# SerialCommunication.net
KiCad netlist of a schematic drawn in Altium Designer
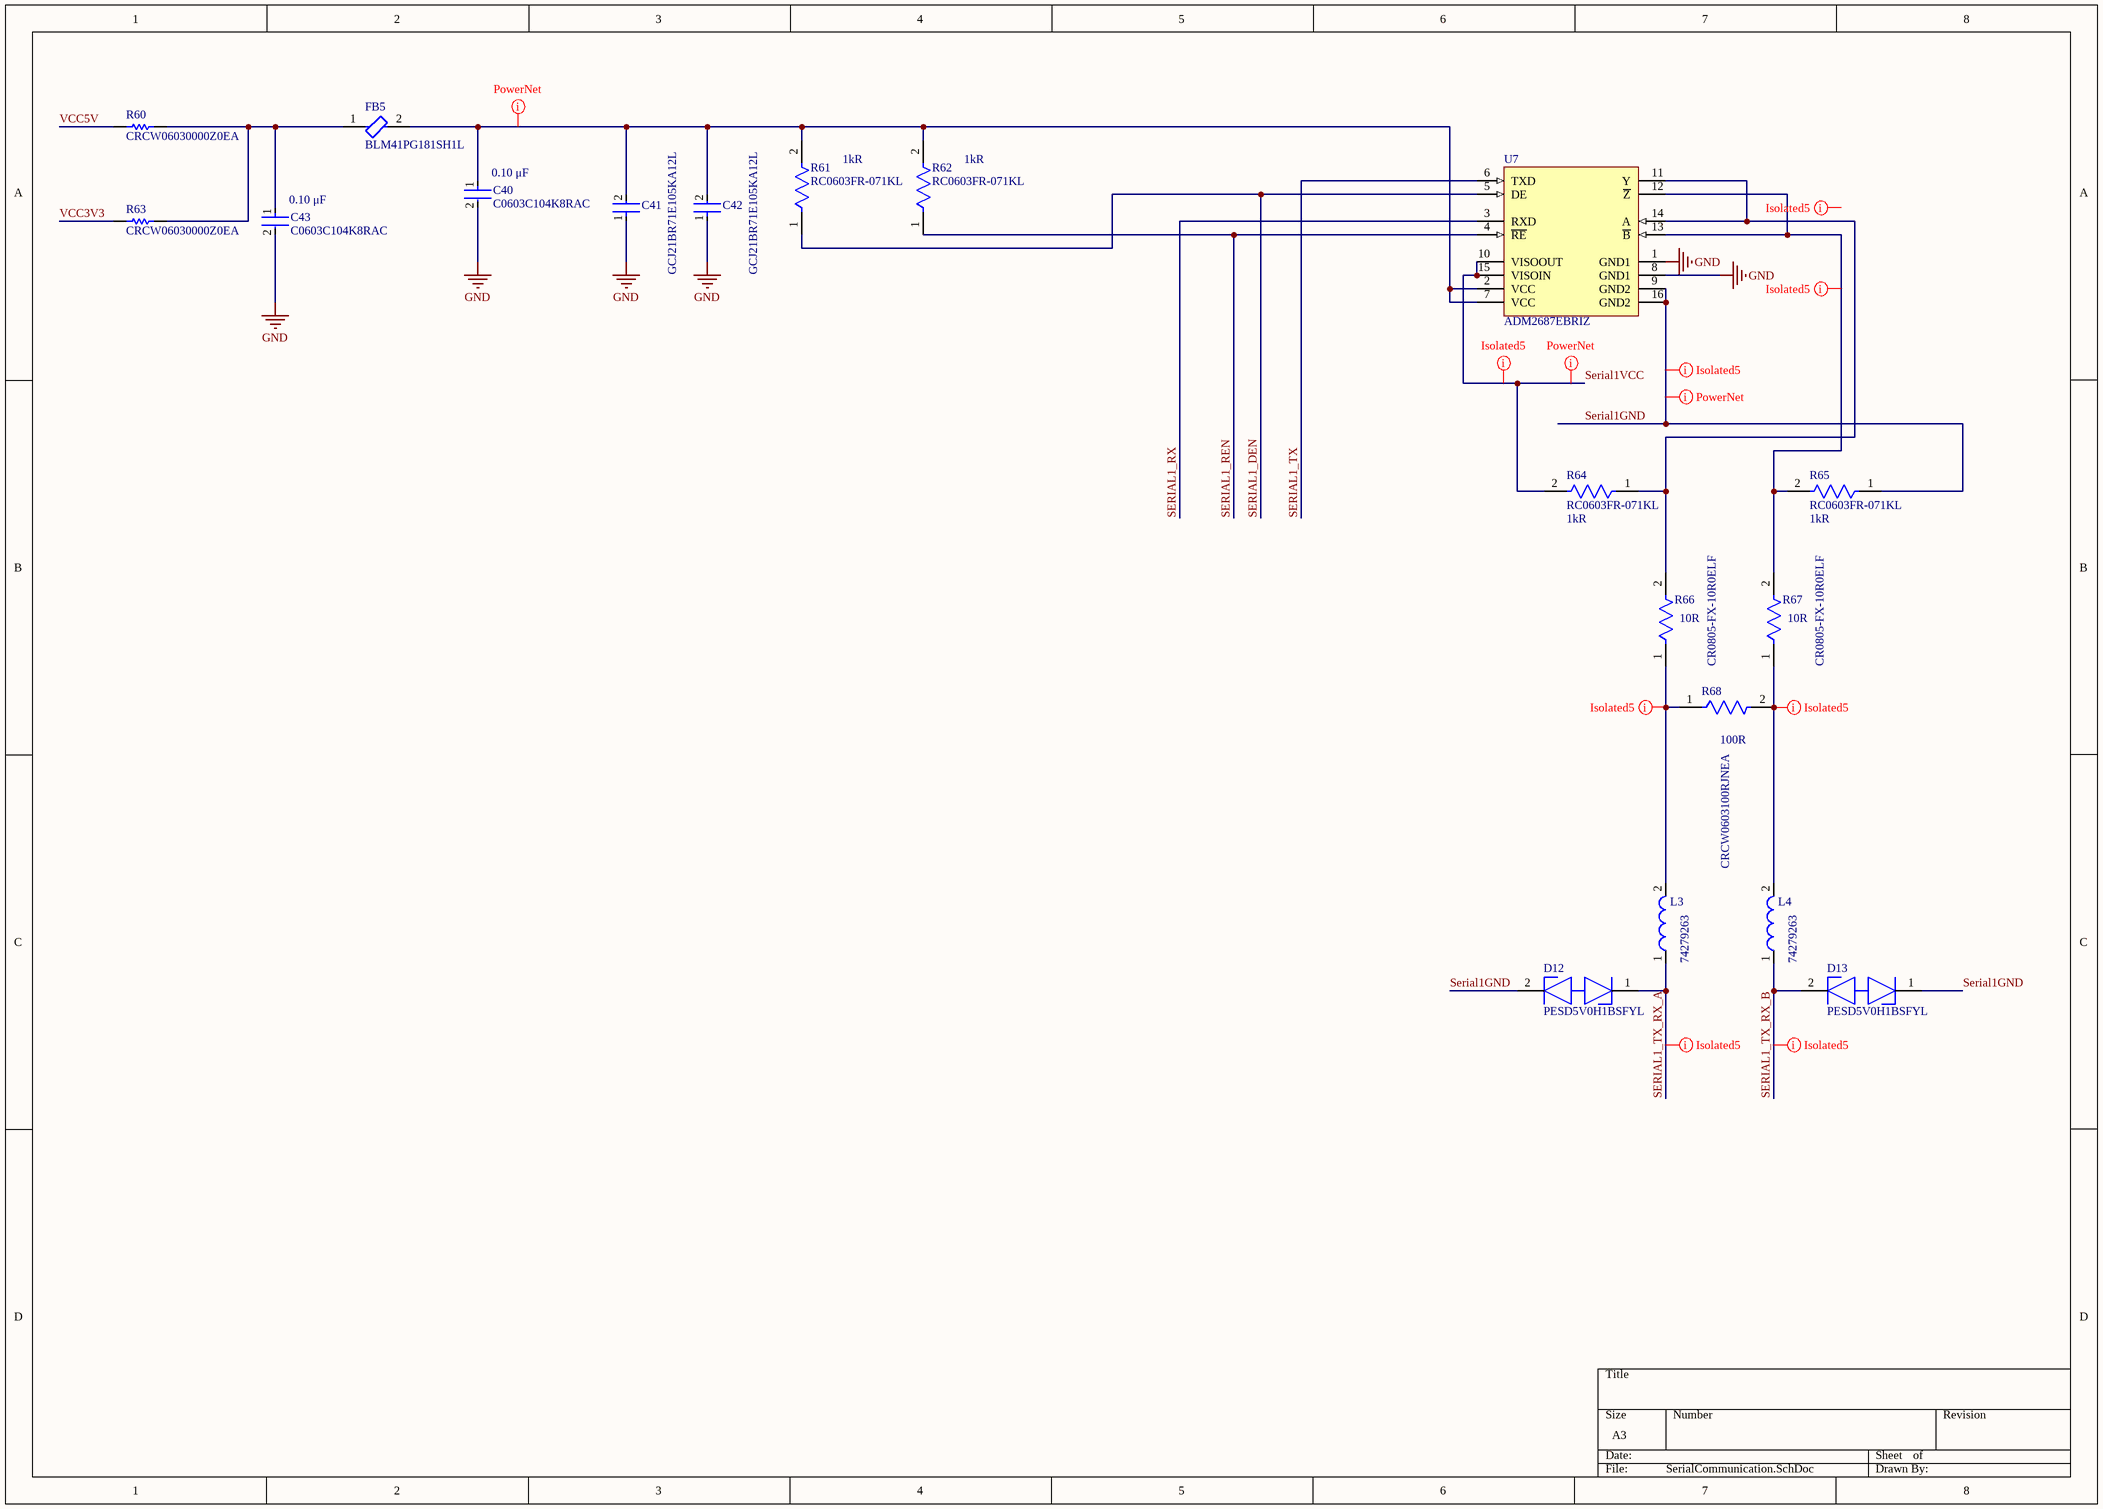
[diagram p0: SerialCommunication.SchDoc]

(export (version "E")
  (design (tool "Eeschema 10.0.6"))
  (components
    (comp (ref "C40")
      (value "C0603C104K8RAC")
      (footprint "FP-C0603C-CF-MFG")
      (description "C0603 0.10 μF X7R 30ppm/°C 10.00% 10 V")
      (fields
        (field (name "MANUFACTURER") "KEMET")
        (field (name "CAPACITANCE") "0.10 μF")
        (field (name "OCTOPART") "https://octopart.com/c0603c104k8rac-kemet-1325403")
      )
      (libsource (lib "Altium Content Vault") (part "b4654b650e69147ec39a6b967a45e02"))
    )
    (comp (ref "C41")
      (value "GCJ21BR71E105KA12L")
      (footprint "FP-GCJ21B-0_3-MFG")
      (description "Multilayer Ceramic Capacitors MLCC - SMD/SMT 0805 1uF 10%, 25VDC,  X7R 15%")
      (fields (field (name "TOLERANCE") "10%"))
      (libsource (lib "Altium Content Vault") (part "02cd4be3c70576c341d710602a673aa"))
    )
    (comp (ref "C42")
      (value "GCJ21BR71E105KA12L")
      (footprint "FP-GCJ21B-0_3-MFG")
      (description "Multilayer Ceramic Capacitors MLCC - SMD/SMT 0805 1uF 10%, 25VDC,  X7R 15%")
      (fields (field (name "TOLERANCE") "10%"))
      (libsource (lib "Altium Content Vault") (part "02cd4be3c70576c341d710602a673aa"))
    )
    (comp (ref "C43")
      (value "C0603C104K8RAC")
      (footprint "FP-C0603C-CF-MFG")
      (description "C0603 0.10 μF X7R 30ppm/°C 10.00% 10 V")
      (fields
        (field (name "MANUFACTURER") "KEMET")
        (field (name "CAPACITANCE") "0.10 μF")
        (field (name "OCTOPART") "https://octopart.com/c0603c104k8rac-kemet-1325403")
      )
      (libsource (lib "Altium Content Vault") (part "b4654b650e69147ec39a6b967a45e02"))
    )
    (comp (ref "D12")
      (value "PESD5V0H1BSFYL")
      (footprint "FP-SOD962-2-MFG")
      (description "TVS DIODE 5V 5V DSN0603-2")
      (fields
        (field (name "OCTOPART") "https://octopart.com/pesd5v0h1bsfyl-nexperia-78741149")
        (field (name "MANUFACTURER") "Nexperia")
      )
      (libsource (lib "Altium Content Vault") (part "35d3c4067516f6c39e60198d779250f"))
    )
    (comp (ref "D13")
      (value "PESD5V0H1BSFYL")
      (footprint "FP-SOD962-2-MFG")
      (description "TVS DIODE 5V 5V DSN0603-2")
      (fields
        (field (name "OCTOPART") "https://octopart.com/pesd5v0h1bsfyl-nexperia-78741149")
        (field (name "MANUFACTURER") "Nexperia")
      )
      (libsource (lib "Altium Content Vault") (part "35d3c4067516f6c39e60198d779250f"))
    )
    (comp (ref "FB5")
      (value "BLM41PG181SH1L")
      (footprint "FP-BLM41-0_2-a1_2-MFG")
      (description "Ferrite Bead, 1806, 180Ω @ 100MHz, 25%, 0.02Ω, 3.5A")
      (fields (field (name "TOLERANCE") "25%"))
      (libsource (lib "Altium Content Vault") (part "5f30dd21d616792df468990f7003faa"))
    )
    (comp (ref "L3")
      (value "74279263")
      (footprint "SMD-0603")
      (description "SMD EMI Suppression Ferrite Bead WE-CBF, Z = 220 Ohm")
      (libsource (lib "Altium Content Vault") (part "PAS-IND-INDUCTOR-2"))
    )
    (comp (ref "L4")
      (value "74279263")
      (footprint "SMD-0603")
      (description "SMD EMI Suppression Ferrite Bead WE-CBF, Z = 220 Ohm")
      (libsource (lib "Altium Content Vault") (part "PAS-IND-INDUCTOR-2"))
    )
    (comp (ref "R60")
      (value "CRCW06030000Z0EA")
      (footprint "RESC1609X50X30NL8T20")
      (description "Chip Resistor, 0 Ohm, Jumper, 100 mW, -55 to 155 degC, 0603 (1608 Metric), RoHS, Tape and Reel")
      (fields (field (name "MANUFACTURER") "Vishay Semiconductor"))
      (libsource (lib "Altium Content Vault") (part "RES-2"))
    )
    (comp (ref "R61")
      (value "RC0603FR-071KL")
      (footprint "FP-RC0603-0_55-IPC_C")
      (description "RES 1K OHM 1% 1/10W 0603")
      (fields (field (name "RESISTANCE") "1kR") (field (name "TOLERANCE") "1%"))
      (libsource (lib "Altium Content Vault") (part "1029c3af85768c4190bb7ad29bc67b5"))
    )
    (comp (ref "R62")
      (value "RC0603FR-071KL")
      (footprint "FP-RC0603-0_55-IPC_C")
      (description "RES 1K OHM 1% 1/10W 0603")
      (fields (field (name "RESISTANCE") "1kR") (field (name "TOLERANCE") "1%"))
      (libsource (lib "Altium Content Vault") (part "1029c3af85768c4190bb7ad29bc67b5"))
    )
    (comp (ref "R63")
      (value "CRCW06030000Z0EA")
      (footprint "RESC1609X50X30NL8T20")
      (description "Chip Resistor, 0 Ohm, Jumper, 100 mW, -55 to 155 degC, 0603 (1608 Metric), RoHS, Tape and Reel")
      (fields (field (name "MANUFACTURER") "Vishay Semiconductor"))
      (libsource (lib "Altium Content Vault") (part "RES-2"))
    )
    (comp (ref "R64")
      (value "RC0603FR-071KL")
      (footprint "FP-RC0603-0_55-IPC_C")
      (description "RES 1K OHM 1% 1/10W 0603")
      (fields (field (name "RESISTANCE") "1kR") (field (name "TOLERANCE") "1%"))
      (libsource (lib "Altium Content Vault") (part "1029c3af85768c4190bb7ad29bc67b5"))
    )
    (comp (ref "R65")
      (value "RC0603FR-071KL")
      (footprint "FP-RC0603-0_55-IPC_C")
      (description "RES 1K OHM 1% 1/10W 0603")
      (fields (field (name "RESISTANCE") "1kR") (field (name "TOLERANCE") "1%"))
      (libsource (lib "Altium Content Vault") (part "1029c3af85768c4190bb7ad29bc67b5"))
    )
    (comp (ref "R66")
      (value "CR0805-FX-10R0ELF")
      (footprint "FP-CR0805-IPC_B")
      (description "Thick Film Chip Resistors 0805 10Ω 0.125W 1% 100ppm/°C")
      (fields (field (name "TOLERANCE") "1%") (field (name "RESISTANCE") "10R"))
      (libsource (lib "Altium Content Vault") (part "1029c3af85768c4190bb7ad29bc67b5"))
    )
    (comp (ref "R67")
      (value "CR0805-FX-10R0ELF")
      (footprint "FP-CR0805-IPC_B")
      (description "Thick Film Chip Resistors 0805 10Ω 0.125W 1% 100ppm/°C")
      (fields (field (name "TOLERANCE") "1%") (field (name "RESISTANCE") "10R"))
      (libsource (lib "Altium Content Vault") (part "1029c3af85768c4190bb7ad29bc67b5"))
    )
    (comp (ref "R68")
      (value "CRCW0603100RJNEA")
      (footprint "FP-CRCW0603-e3-IPC_B")
      (description "RES Thick Film, 100Ω, 5%, 0.1W, 200ppm/°C, 0603")
      (fields (field (name "RESISTANCE") "100R") (field (name "TOLERANCE") "5%"))
      (libsource (lib "Altium Content Vault") (part "1029c3af85768c4190bb7ad29bc67b5"))
    )
    (comp (ref "U7")
      (value "ADM2687EBRIZ")
      (footprint "ADI-RI-16-2_L")
      (fields (field (name "MANUFACTURER") "Analog Devices"))
      (libsource (lib "Altium Content Vault") (part "ADI-ADM268X-RI-16-2"))
    )
  )
  (nets
    (net (code "1") (name "/SERIAL1_DEN") (class "Default")
      (node (ref "R61") (pin "1") (pinfunction "1_1") (pintype "passive"))
      (node (ref "U7") (pin "5") (pinfunction "DE_5") (pintype "input"))
    )
    (net (code "2") (name "/SERIAL1_REN") (class "Default")
      (node (ref "R62") (pin "1") (pinfunction "1_1") (pintype "passive"))
      (node (ref "U7") (pin "4") (pinfunction "~{RE}_4") (pintype "input"))
    )
    (net (code "3") (name "/SERIAL1_RX") (class "Default")
      (node (ref "U7") (pin "3") (pinfunction "RXD_3") (pintype "tri_state"))
    )
    (net (code "4") (name "/SERIAL1_TX") (class "Default")
      (node (ref "U7") (pin "6") (pinfunction "TXD_6") (pintype "input"))
    )
    (net (code "5") (name "/SERIAL1_TX_RX_A") (class "Default")
      (node (ref "D12") (pin "1") (pinfunction "K1_1") (pintype "passive"))
      (node (ref "L3") (pin "1") (pinfunction "1_1") (pintype "passive"))
    )
    (net (code "6") (name "/SERIAL1_TX_RX_B") (class "Default")
      (node (ref "D13") (pin "2") (pinfunction "K2_2") (pintype "passive"))
      (node (ref "L4") (pin "1") (pinfunction "1_1") (pintype "passive"))
    )
    (net (code "7") (name "/Serial1GND") (class "Default")
      (node (ref "D12") (pin "2") (pinfunction "K2_2") (pintype "passive"))
      (node (ref "D13") (pin "1") (pinfunction "K1_1") (pintype "passive"))
      (node (ref "R65") (pin "1") (pinfunction "1_1") (pintype "passive"))
      (node (ref "U7") (pin "16") (pinfunction "GND2_16") (pintype "power_in"))
      (node (ref "U7") (pin "9") (pinfunction "GND2_9") (pintype "power_in"))
    )
    (net (code "8") (name "/Serial1VCC") (class "Default")
      (node (ref "R64") (pin "2") (pinfunction "2_2") (pintype "passive"))
      (node (ref "U7") (pin "10") (pinfunction "VISOOUT_10") (pintype "power_in"))
      (node (ref "U7") (pin "15") (pinfunction "VISOIN_15") (pintype "power_in"))
    )
    (net (code "9") (name "/VCC3V3") (class "Default")
      (node (ref "R63") (pin "1") (pinfunction "1_1") (pintype "passive"))
    )
    (net (code "10") (name "/VCC5V") (class "Default")
      (node (ref "R60") (pin "1") (pinfunction "1_1") (pintype "passive"))
    )
    (net (code "11") (name "GND") (class "Default")
      (node (ref "C40") (pin "2") (pinfunction "2_2") (pintype "passive"))
      (node (ref "C41") (pin "1") (pinfunction "1_1") (pintype "passive"))
      (node (ref "C42") (pin "1") (pinfunction "1_1") (pintype "passive"))
      (node (ref "C43") (pin "2") (pinfunction "2_2") (pintype "passive"))
      (node (ref "U7") (pin "1") (pinfunction "GND1_1") (pintype "power_in"))
      (node (ref "U7") (pin "8") (pinfunction "GND1_8") (pintype "power_in"))
    )
    (net (code "12") (name "Net-(C40-Pad1)") (class "Default")
      (node (ref "C40") (pin "1") (pinfunction "1_1") (pintype "passive"))
      (node (ref "C41") (pin "2") (pinfunction "2_2") (pintype "passive"))
      (node (ref "C42") (pin "2") (pinfunction "2_2") (pintype "passive"))
      (node (ref "FB5") (pin "2") (pinfunction "2_2") (pintype "passive"))
      (node (ref "R61") (pin "2") (pinfunction "2_2") (pintype "passive"))
      (node (ref "R62") (pin "2") (pinfunction "2_2") (pintype "passive"))
      (node (ref "U7") (pin "2") (pinfunction "VCC_2") (pintype "power_in"))
      (node (ref "U7") (pin "7") (pinfunction "VCC_7") (pintype "power_in"))
    )
    (net (code "13") (name "Net-(C43-Pad1)") (class "Default")
      (node (ref "C43") (pin "1") (pinfunction "1_1") (pintype "passive"))
      (node (ref "FB5") (pin "1") (pinfunction "1_1") (pintype "passive"))
      (node (ref "R60") (pin "2") (pinfunction "2_2") (pintype "passive"))
      (node (ref "R63") (pin "2") (pinfunction "2_2") (pintype "passive"))
    )
    (net (code "14") (name "Net-(L3-Pad2)") (class "Default")
      (node (ref "L3") (pin "2") (pinfunction "2_2") (pintype "passive"))
      (node (ref "R66") (pin "1") (pinfunction "1_1") (pintype "passive"))
      (node (ref "R68") (pin "1") (pinfunction "1_1") (pintype "passive"))
    )
    (net (code "15") (name "Net-(L4-Pad2)") (class "Default")
      (node (ref "L4") (pin "2") (pinfunction "2_2") (pintype "passive"))
      (node (ref "R67") (pin "1") (pinfunction "1_1") (pintype "passive"))
      (node (ref "R68") (pin "2") (pinfunction "2_2") (pintype "passive"))
    )
    (net (code "16") (name "Net-(U7-A)") (class "Default")
      (node (ref "R64") (pin "1") (pinfunction "1_1") (pintype "passive"))
      (node (ref "R66") (pin "2") (pinfunction "2_2") (pintype "passive"))
      (node (ref "U7") (pin "11") (pinfunction "Y_11") (pintype "tri_state"))
      (node (ref "U7") (pin "14") (pinfunction "A_14") (pintype "input"))
    )
    (net (code "17") (name "Net-(U7-~{B})") (class "Default")
      (node (ref "R65") (pin "2") (pinfunction "2_2") (pintype "passive"))
      (node (ref "R67") (pin "2") (pinfunction "2_2") (pintype "passive"))
      (node (ref "U7") (pin "12") (pinfunction "~{Z}_12") (pintype "tri_state"))
      (node (ref "U7") (pin "13") (pinfunction "~{B}_13") (pintype "input"))
    )
  )
)
